# Switch.net
KiCad netlist of a schematic drawn in Altium Designer
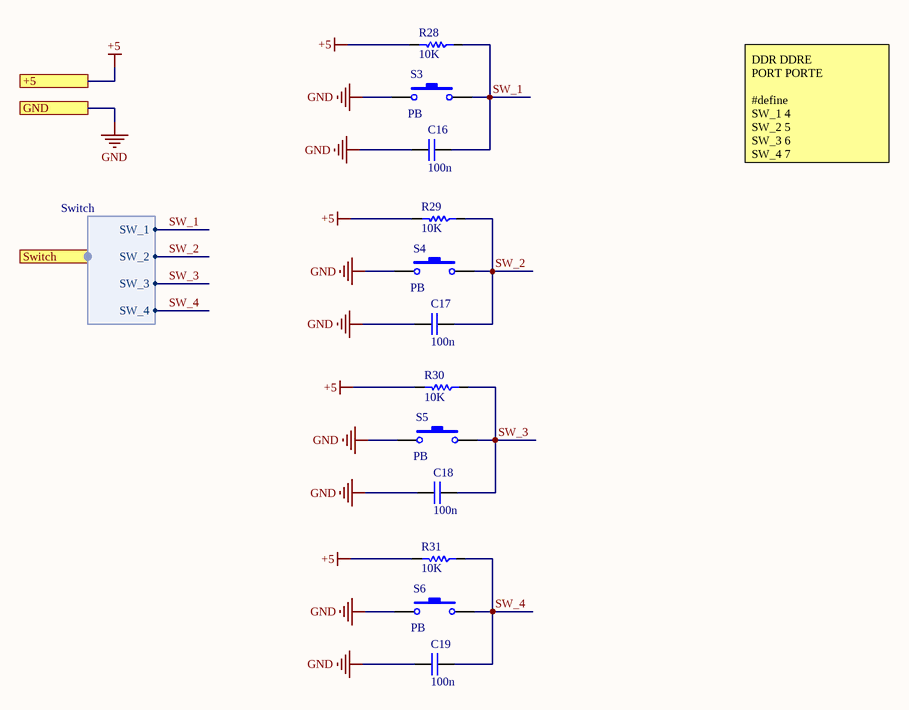
[diagram p0: Switch.SchDoc]

(export (version "E")
  (design (tool "Eeschema 10.0.6"))
  (components
    (comp (ref "C16")
      (value "100n")
      (footprint "CAP 1206/3216")
      (description "Bipolar ceramic capacitor SMD")
      (fields (field (name "VALIDATION") "Valid"))
      (libsource (lib "aKaReZa") (part "Cap_Multi_SMD_100nF_1206"))
    )
    (comp (ref "C17")
      (value "100n")
      (footprint "CAP 1206/3216")
      (description "Bipolar ceramic capacitor SMD")
      (fields (field (name "VALIDATION") "Valid"))
      (libsource (lib "aKaReZa") (part "Cap_Multi_SMD_100nF_1206"))
    )
    (comp (ref "C18")
      (value "100n")
      (footprint "CAP 1206/3216")
      (description "Bipolar ceramic capacitor SMD")
      (fields (field (name "VALIDATION") "Valid"))
      (libsource (lib "aKaReZa") (part "Cap_Multi_SMD_100nF_1206"))
    )
    (comp (ref "C19")
      (value "100n")
      (footprint "CAP 1206/3216")
      (description "Bipolar ceramic capacitor SMD")
      (fields (field (name "VALIDATION") "Valid"))
      (libsource (lib "aKaReZa") (part "Cap_Multi_SMD_100nF_1206"))
    )
    (comp (ref "R28")
      (value "10K")
      (footprint "RES 1206 (3216X08L)")
      (description "Resistor")
      (fields (field (name "VALIDATION") "Valid"))
      (libsource (lib "aKaReZa") (part "Res_SMD_1206"))
    )
    (comp (ref "R29")
      (value "10K")
      (footprint "RES 1206 (3216X08L)")
      (description "Resistor")
      (fields (field (name "VALIDATION") "Valid"))
      (libsource (lib "aKaReZa") (part "Res_SMD_1206"))
    )
    (comp (ref "R30")
      (value "10K")
      (footprint "RES 1206 (3216X08L)")
      (description "Resistor")
      (fields (field (name "VALIDATION") "Valid"))
      (libsource (lib "aKaReZa") (part "Res_SMD_1206"))
    )
    (comp (ref "R31")
      (value "10K")
      (footprint "RES 1206 (3216X08L)")
      (description "Resistor")
      (fields (field (name "VALIDATION") "Valid"))
      (libsource (lib "aKaReZa") (part "Res_SMD_1206"))
    )
    (comp (ref "S3")
      (value "PB")
      (footprint "SW_PB_SMD_2PIN_SPST_6X3X2")
      (description "SMT Tactile ‎Switch")
      (fields (field (name "VALIDATION") "Valid"))
      (libsource (lib "aKaReZa") (part "SW_PushButton_2_SMD"))
    )
    (comp (ref "S4")
      (value "PB")
      (footprint "SW_PB_SMD_2PIN_SPST_6X3X2")
      (description "SMT Tactile ‎Switch")
      (fields (field (name "VALIDATION") "Valid"))
      (libsource (lib "aKaReZa") (part "SW_PushButton_2_SMD"))
    )
    (comp (ref "S5")
      (value "PB")
      (footprint "SW_PB_SMD_2PIN_SPST_6X3X2")
      (description "SMT Tactile ‎Switch")
      (fields (field (name "VALIDATION") "Valid"))
      (libsource (lib "aKaReZa") (part "SW_PushButton_2_SMD"))
    )
    (comp (ref "S6")
      (value "PB")
      (footprint "SW_PB_SMD_2PIN_SPST_6X3X2")
      (description "SMT Tactile ‎Switch")
      (fields (field (name "VALIDATION") "Valid"))
      (libsource (lib "aKaReZa") (part "SW_PushButton_2_SMD"))
    )
  )
  (nets
    (net (code "2") (name "+5") (class "Default")
      (node (ref "R28") (pin "2") (pinfunction "2_2") (pintype "passive"))
      (node (ref "R29") (pin "2") (pinfunction "2_2") (pintype "passive"))
      (node (ref "R30") (pin "2") (pinfunction "2_2") (pintype "passive"))
      (node (ref "R31") (pin "2") (pinfunction "2_2") (pintype "passive"))
    )
    (net (code "3") (name "/SW_1") (class "Default")
      (node (ref "C16") (pin "1") (pinfunction "1_1") (pintype "passive"))
      (node (ref "R28") (pin "1") (pinfunction "1_1") (pintype "passive"))
      (node (ref "S3") (pin "2") (pinfunction "2_2") (pintype "passive"))
    )
    (net (code "4") (name "/SW_2") (class "Default")
      (node (ref "C17") (pin "1") (pinfunction "1_1") (pintype "passive"))
      (node (ref "R29") (pin "1") (pinfunction "1_1") (pintype "passive"))
      (node (ref "S4") (pin "2") (pinfunction "2_2") (pintype "passive"))
    )
    (net (code "5") (name "/SW_3") (class "Default")
      (node (ref "C18") (pin "1") (pinfunction "1_1") (pintype "passive"))
      (node (ref "R30") (pin "1") (pinfunction "1_1") (pintype "passive"))
      (node (ref "S5") (pin "2") (pinfunction "2_2") (pintype "passive"))
    )
    (net (code "6") (name "/SW_4") (class "Default")
      (node (ref "C19") (pin "1") (pinfunction "1_1") (pintype "passive"))
      (node (ref "R31") (pin "1") (pinfunction "1_1") (pintype "passive"))
      (node (ref "S6") (pin "2") (pinfunction "2_2") (pintype "passive"))
    )
    (net (code "8") (name "GND") (class "Default")
      (node (ref "C16") (pin "2") (pinfunction "2_2") (pintype "passive"))
      (node (ref "C17") (pin "2") (pinfunction "2_2") (pintype "passive"))
      (node (ref "C18") (pin "2") (pinfunction "2_2") (pintype "passive"))
      (node (ref "C19") (pin "2") (pinfunction "2_2") (pintype "passive"))
      (node (ref "S3") (pin "1") (pinfunction "1_1") (pintype "passive"))
      (node (ref "S4") (pin "1") (pinfunction "1_1") (pintype "passive"))
      (node (ref "S5") (pin "1") (pinfunction "1_1") (pintype "passive"))
      (node (ref "S6") (pin "1") (pinfunction "1_1") (pintype "passive"))
    )
  )
)
